# Sensors.net
KiCad netlist of a schematic drawn in Altium Designer
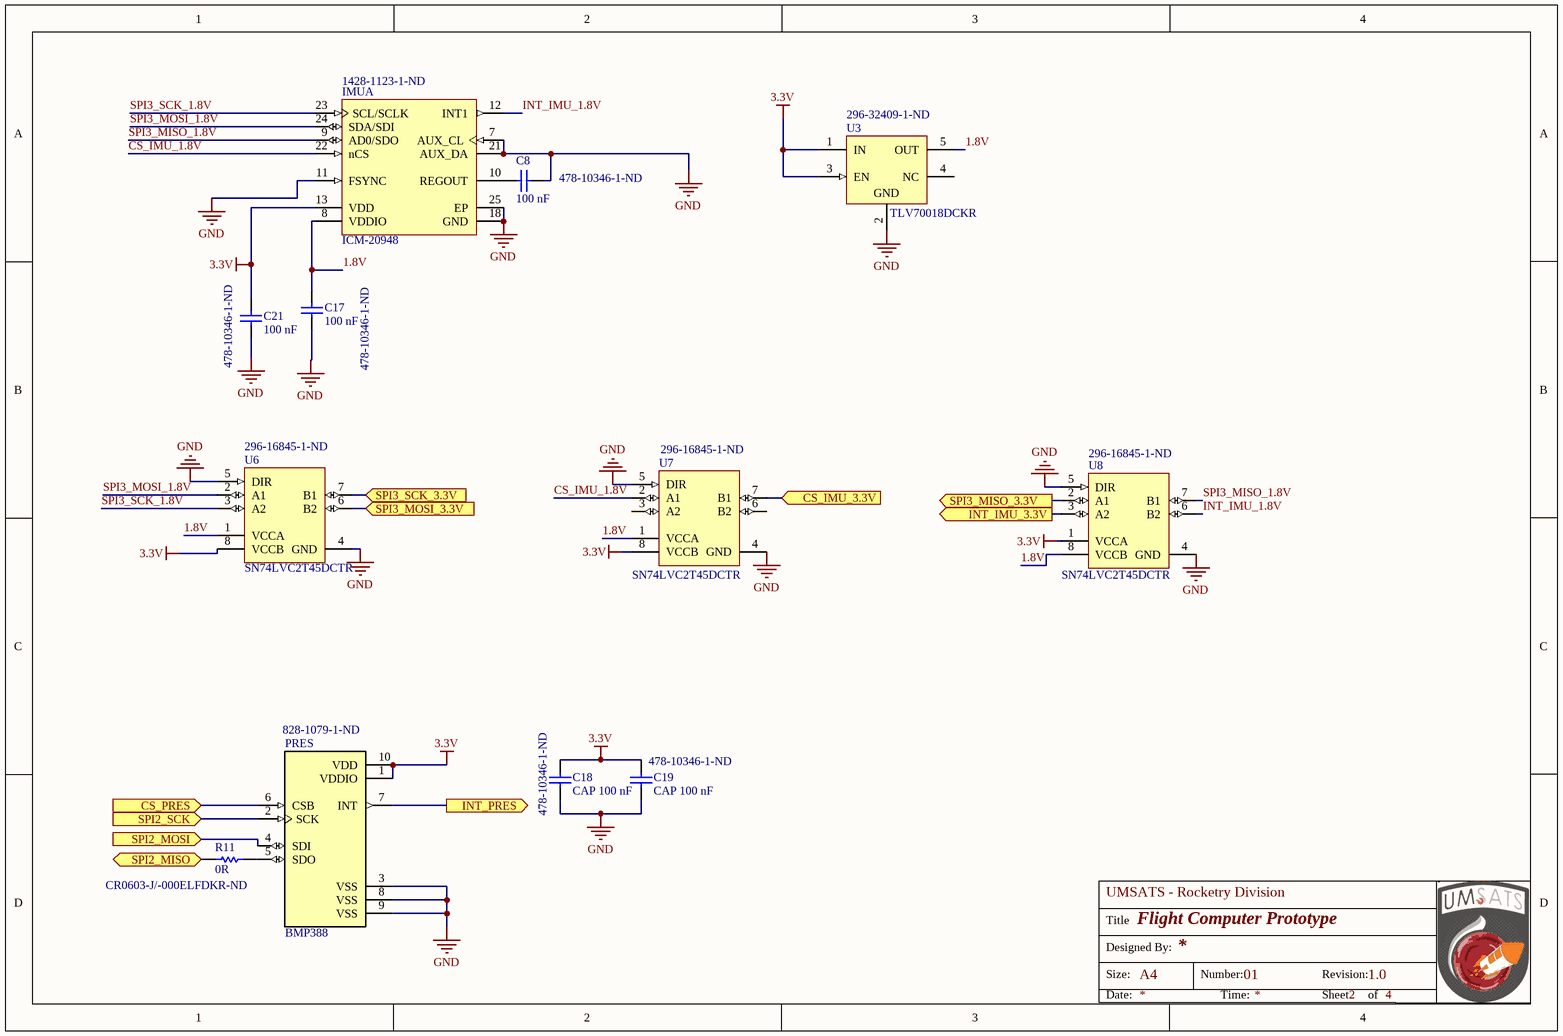
[diagram p0: Sensors.SchDoc]

(export (version "E")
  (design (tool "Eeschema 10.0.6"))
  (components
    (comp (ref "C8")
      (value "100 nF")
      (footprint "CAPC1608X90X35ML15T15")
      (fields
        (field (name "PART NUMBER") "06035C104K4Z2A")
        (field (name "MANUFACTURER") "AVX Interconnect / Elco")
        (field (name "SUPPLIER PART NUMBER 1") "478-10346-1-ND")
      )
      (libsource (lib "Altium Content Vault") (part "CAP"))
    )
    (comp (ref "C17")
      (value "100 nF")
      (footprint "CAPC1608X90X35ML15T15")
      (fields
        (field (name "PART NUMBER") "06035C104K4Z2A")
        (field (name "MANUFACTURER") "AVX Interconnect / Elco")
        (field (name "SUPPLIER PART NUMBER 1") "478-10346-1-ND")
      )
      (libsource (lib "Altium Content Vault") (part "CAP"))
    )
    (comp (ref "C18")
      (value "CAP 100 nF")
      (footprint "06035C104KAT4A")
      (description "Capacitor")
      (fields
        (field (name "SUPPLIER PART NUMBER 1") "478-10346-1-ND")
        (field (name "PUBLISHER") "Altium Limited")
      )
      (libsource (lib "Miscellaneous Devices") (part "Cap"))
    )
    (comp (ref "C19")
      (value "CAP 100 nF")
      (footprint "06035C104KAT4A")
      (description "Capacitor")
      (fields
        (field (name "SUPPLIER PART NUMBER 1") "478-10346-1-ND")
        (field (name "PUBLISHER") "Altium Limited")
      )
      (libsource (lib "Miscellaneous Devices") (part "Cap"))
    )
    (comp (ref "C21")
      (value "100 nF")
      (footprint "CAPC1608X90X35ML15T15")
      (fields
        (field (name "PART NUMBER") "06035C104K4Z2A")
        (field (name "MANUFACTURER") "AVX Interconnect / Elco")
        (field (name "SUPPLIER PART NUMBER 1") "478-10346-1-ND")
      )
      (libsource (lib "Altium Content Vault") (part "CAP"))
    )
    (comp (ref "IMU")
      (value "ICM-20948")
      (footprint "TDK-QFN-24_L")
      (fields (field (name "MANUFACTURER") "TDK") (field (name "SUPPLIER PART NUMBER 1") "1428-1123-1-ND"))
      (libsource (lib "Altium Content Vault") (part "TDK-ICM-20948-QFN-24"))
    )
    (comp (ref "PRES")
      (value "BMP388")
      (footprint "*PQFN50P200X200X80-10N")
      (description "P-Sensor SPI I2C 1, 25 Bar SMD")
      (fields (field (name "MF") "Bosch Sensortec") (field (name "SUPPLIER PART NUMBER 1") "828-1079-1-ND"))
      (libsource (lib "BMP388") (part "BMP388"))
    )
    (comp (ref "R11")
      (value "0R")
      (footprint "CR0603-J/-000ELF")
      (description "Resistor")
      (fields
        (field (name "SUPPLIER PART NUMBER 1") "CR0603-J/-000ELFDKR-ND")
        (field (name "PUBLISHER") "Altium Limited")
      )
      (libsource (lib "Miscellaneous Devices") (part "Res1"))
    )
    (comp (ref "U3")
      (value "TLV70018DCKR")
      (footprint "DCK0005A_N")
      (fields
        (field (name "MANUFACTURER") "Texas Instruments")
        (field (name "SUPPLIER PART NUMBER 1") "296-32409-1-ND")
      )
      (libsource (lib "Altium Content Vault") (part "TI-TXX7XXXX-5"))
    )
    (comp (ref "U6")
      (value "SN74LVC2T45DCTR")
      (footprint "DCU0008A_N")
      (fields
        (field (name "MANUFACTURER") "Texas Instruments")
        (field (name "GENERIC PART NUMBER") "SN74LVC2T45")
        (field (name "SUPPLIER PART NUMBER 1") "296-16845-1-ND")
      )
      (libsource (lib "Altium Content Vault") (part "TI-SN74XVC2T45-8"))
    )
    (comp (ref "U7")
      (value "SN74LVC2T45DCTR")
      (footprint "DCU0008A_N")
      (fields
        (field (name "MANUFACTURER") "Texas Instruments")
        (field (name "GENERIC PART NUMBER") "SN74LVC2T45")
        (field (name "SUPPLIER PART NUMBER 1") "296-16845-1-ND")
      )
      (libsource (lib "Altium Content Vault") (part "TI-SN74XVC2T45-8"))
    )
    (comp (ref "U8")
      (value "SN74LVC2T45DCTR")
      (footprint "DCU0008A_N")
      (fields
        (field (name "MANUFACTURER") "Texas Instruments")
        (field (name "GENERIC PART NUMBER") "SN74LVC2T45")
        (field (name "SUPPLIER PART NUMBER 1") "296-16845-1-ND")
      )
      (libsource (lib "Altium Content Vault") (part "TI-SN74XVC2T45-8"))
    )
  )
  (nets
    (net (code "1") (name "/1.8V") (class "Default")
      (node (ref "C17") (pin "2") (pinfunction "2_2") (pintype "passive"))
      (node (ref "IMU") (pin "8") (pinfunction "VDDIO_8") (pintype "power_in"))
      (node (ref "U3") (pin "5") (pinfunction "OUT_5") (pintype "power_in"))
      (node (ref "U6") (pin "1") (pinfunction "VCCA_1") (pintype "power_in"))
      (node (ref "U7") (pin "1") (pinfunction "VCCA_1") (pintype "power_in"))
      (node (ref "U8") (pin "8") (pinfunction "VCCB_8") (pintype "power_in"))
    )
    (net (code "2") (name "/CS_IMU_1.8V") (class "Default")
      (node (ref "IMU") (pin "22") (pinfunction "nCS_22") (pintype "input"))
      (node (ref "U7") (pin "2") (pinfunction "A1_2") (pintype "bidirectional"))
    )
    (net (code "3") (name "/CS_IMU_3.3V") (class "Default")
      (node (ref "U7") (pin "7") (pinfunction "B1_7") (pintype "bidirectional"))
    )
    (net (code "4") (name "/CS_PRES") (class "Default")
      (node (ref "PRES") (pin "6") (pinfunction "CSB_6") (pintype "input"))
    )
    (net (code "5") (name "/INT_IMU_1.8V") (class "Default")
      (node (ref "IMU") (pin "12") (pinfunction "INT1_12") (pintype "output"))
      (node (ref "U8") (pin "6") (pinfunction "B2_6") (pintype "bidirectional"))
    )
    (net (code "6") (name "/INT_IMU_3.3V") (class "Default")
      (node (ref "U8") (pin "3") (pinfunction "A2_3") (pintype "bidirectional"))
    )
    (net (code "7") (name "/INT_PRES") (class "Default")
      (node (ref "PRES") (pin "7") (pinfunction "INT_7") (pintype "output"))
    )
    (net (code "8") (name "/SPI2_MISO") (class "Default")
      (node (ref "R11") (pin "1") (pinfunction "1_1") (pintype "passive"))
    )
    (net (code "9") (name "/SPI2_MOSI") (class "Default")
      (node (ref "PRES") (pin "4") (pinfunction "SDI_4") (pintype "bidirectional"))
    )
    (net (code "10") (name "/SPI2_SCK") (class "Default")
      (node (ref "PRES") (pin "2") (pinfunction "SCK_2") (pintype "input"))
    )
    (net (code "11") (name "/SPI3_MISO_1.8V") (class "Default")
      (node (ref "IMU") (pin "9") (pinfunction "AD0/SDO_9") (pintype "bidirectional"))
      (node (ref "U8") (pin "7") (pinfunction "B1_7") (pintype "bidirectional"))
    )
    (net (code "12") (name "/SPI3_MISO_3.3V") (class "Default")
      (node (ref "U8") (pin "2") (pinfunction "A1_2") (pintype "bidirectional"))
    )
    (net (code "13") (name "/SPI3_MOSI_1.8V") (class "Default")
      (node (ref "IMU") (pin "24") (pinfunction "SDA/SDI_24") (pintype "bidirectional"))
      (node (ref "U6") (pin "2") (pinfunction "A1_2") (pintype "bidirectional"))
    )
    (net (code "14") (name "/SPI3_MOSI_3.3V") (class "Default")
      (node (ref "U6") (pin "6") (pinfunction "B2_6") (pintype "bidirectional"))
    )
    (net (code "15") (name "/SPI3_SCK_1.8V") (class "Default")
      (node (ref "IMU") (pin "23") (pinfunction "SCL/SCLK_23") (pintype "input"))
      (node (ref "U6") (pin "3") (pinfunction "A2_3") (pintype "bidirectional"))
    )
    (net (code "16") (name "/SPI3_SCK_3.3V") (class "Default")
      (node (ref "U6") (pin "7") (pinfunction "B1_7") (pintype "bidirectional"))
    )
    (net (code "17") (name "3.3V") (class "Default")
      (node (ref "C18") (pin "1") (pinfunction "1_1") (pintype "passive"))
      (node (ref "C19") (pin "1") (pinfunction "1_1") (pintype "passive"))
      (node (ref "C21") (pin "2") (pinfunction "2_2") (pintype "passive"))
      (node (ref "IMU") (pin "13") (pinfunction "VDD_13") (pintype "power_in"))
      (node (ref "PRES") (pin "1") (pinfunction "VDDIO_1") (pintype "power_in"))
      (node (ref "PRES") (pin "10") (pinfunction "VDD_10") (pintype "power_in"))
      (node (ref "U3") (pin "1") (pinfunction "IN_1") (pintype "power_in"))
      (node (ref "U3") (pin "3") (pinfunction "EN_3") (pintype "input"))
      (node (ref "U6") (pin "8") (pinfunction "VCCB_8") (pintype "power_in"))
      (node (ref "U7") (pin "8") (pinfunction "VCCB_8") (pintype "power_in"))
      (node (ref "U8") (pin "1") (pinfunction "VCCA_1") (pintype "power_in"))
    )
    (net (code "18") (name "GND") (class "Default")
      (node (ref "C17") (pin "1") (pinfunction "1_1") (pintype "passive"))
      (node (ref "C18") (pin "2") (pinfunction "2_2") (pintype "passive"))
      (node (ref "C19") (pin "2") (pinfunction "2_2") (pintype "passive"))
      (node (ref "C21") (pin "1") (pinfunction "1_1") (pintype "passive"))
      (node (ref "C8") (pin "2") (pinfunction "2_2") (pintype "passive"))
      (node (ref "IMU") (pin "11") (pinfunction "FSYNC_11") (pintype "input"))
      (node (ref "IMU") (pin "18") (pinfunction "GND_18") (pintype "power_in"))
      (node (ref "IMU") (pin "21") (pinfunction "AUX_DA_21") (pintype "passive"))
      (node (ref "IMU") (pin "25") (pinfunction "EP_25") (pintype "passive"))
      (node (ref "IMU") (pin "7") (pinfunction "AUX_CL_7") (pintype "input"))
      (node (ref "PRES") (pin "3") (pinfunction "VSS_3") (pintype "power_in"))
      (node (ref "PRES") (pin "8") (pinfunction "VSS_8") (pintype "power_in"))
      (node (ref "PRES") (pin "9") (pinfunction "VSS_9") (pintype "power_in"))
      (node (ref "U3") (pin "2") (pinfunction "GND_2") (pintype "power_in"))
      (node (ref "U6") (pin "4") (pinfunction "GND_4") (pintype "power_in"))
      (node (ref "U6") (pin "5") (pinfunction "DIR_5") (pintype "input"))
      (node (ref "U7") (pin "4") (pinfunction "GND_4") (pintype "power_in"))
      (node (ref "U7") (pin "5") (pinfunction "DIR_5") (pintype "input"))
      (node (ref "U8") (pin "4") (pinfunction "GND_4") (pintype "power_in"))
      (node (ref "U8") (pin "5") (pinfunction "DIR_5") (pintype "input"))
    )
    (net (code "19") (name "Net-(IMUA-REGOUT)") (class "Default")
      (node (ref "C8") (pin "1") (pinfunction "1_1") (pintype "passive"))
      (node (ref "IMU") (pin "10") (pinfunction "REGOUT_10") (pintype "passive"))
    )
    (net (code "20") (name "Net-(PRES-SDO)") (class "Default")
      (node (ref "PRES") (pin "5") (pinfunction "SDO_5") (pintype "bidirectional"))
      (node (ref "R11") (pin "2") (pinfunction "2_2") (pintype "passive"))
    )
    (net (code "21") (name "unconnected-(U3-NC-Pad4)") (class "Default")
      (node (ref "U3") (pin "4") (pinfunction "NC_4") (pintype "passive"))
    )
    (net (code "22") (name "unconnected-(U7-A2-Pad3)") (class "Default")
      (node (ref "U7") (pin "3") (pinfunction "A2_3") (pintype "bidirectional"))
    )
    (net (code "23") (name "unconnected-(U7-B2-Pad6)") (class "Default")
      (node (ref "U7") (pin "6") (pinfunction "B2_6") (pintype "bidirectional"))
    )
  )
)
